# OneMotor.net
KiCad netlist of a schematic drawn in Altium Designer
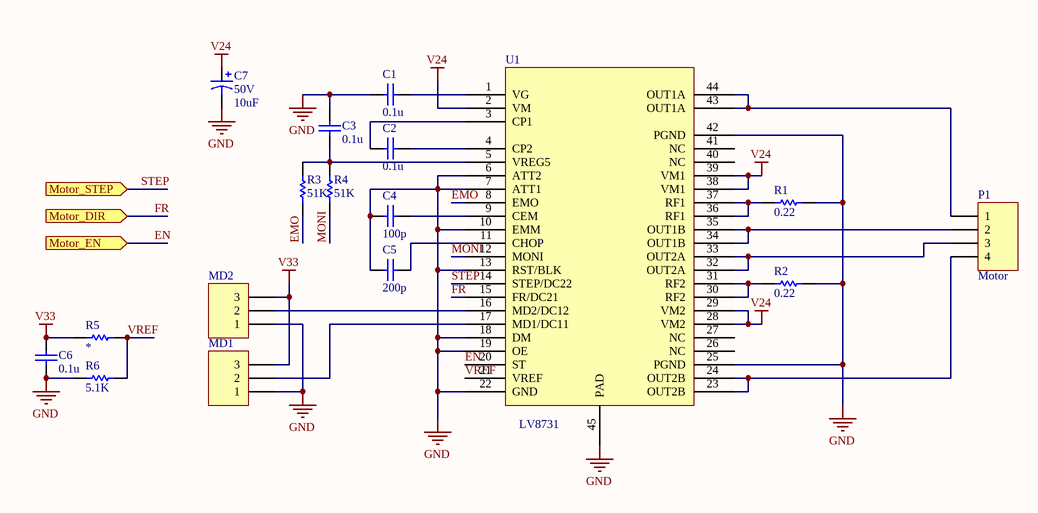
[diagram p0: OneMotor.SchDoc]

(export (version "E")
  (design (tool "Eeschema 10.0.6"))
  (components
    (comp (ref "C1")
      (value "0.1u")
      (footprint "C-1608[0603]")
      (description "Capacitor (Semiconductor SIM Model)")
      (fields (field (name "Comment") "Cap Semi") (field (name "PUBLISHER") "Altium Limited"))
      (libsource (lib "Miscellaneous Devices") (part "Cap Semi"))
    )
    (comp (ref "C2")
      (value "0.1u")
      (footprint "C-1608[0603]")
      (description "Capacitor (Semiconductor SIM Model)")
      (fields (field (name "Comment") "Cap Semi") (field (name "PUBLISHER") "Altium Limited"))
      (libsource (lib "Miscellaneous Devices") (part "Cap Semi"))
    )
    (comp (ref "C3")
      (value "0.1u")
      (footprint "C-1608[0603]")
      (description "Capacitor (Semiconductor SIM Model)")
      (fields (field (name "Comment") "Cap Semi") (field (name "PUBLISHER") "Altium Limited"))
      (libsource (lib "Miscellaneous Devices") (part "Cap Semi"))
    )
    (comp (ref "C4")
      (value "100p")
      (footprint "C-1608[0603]")
      (description "Capacitor (Semiconductor SIM Model)")
      (fields (field (name "Comment") "Cap Semi") (field (name "PUBLISHER") "Altium Limited"))
      (libsource (lib "Miscellaneous Devices") (part "Cap Semi"))
    )
    (comp (ref "C5")
      (value "200p")
      (footprint "C-1608[0603]")
      (description "Capacitor (Semiconductor SIM Model)")
      (fields (field (name "Comment") "Cap Semi") (field (name "PUBLISHER") "Altium Limited"))
      (libsource (lib "Miscellaneous Devices") (part "Cap Semi"))
    )
    (comp (ref "C6")
      (value "0.1u")
      (footprint "C-1608[0603]")
      (description "Capacitor (Semiconductor SIM Model)")
      (fields (field (name "Comment") "Cap Semi") (field (name "PUBLISHER") "Altium Limited"))
      (libsource (lib "Miscellaneous Devices") (part "Cap Semi"))
    )
    (comp (ref "C7")
      (value "50V")
      (footprint "RB.1/.25")
      (description "Polarized Capacitor (Radial)")
      (fields (field (name "ALTIUM_VALUE") "10uF") (field (name "PUBLISHER") "Altium Limited"))
      (libsource (lib "Miscellaneous Devices") (part "Cap Pol1"))
    )
    (comp (ref "MD1")
      (value "Header 3")
      (footprint "shortPad")
      (description "Header, 3-Pin")
      (fields (field (name "PUBLISHER") "Altium Limited"))
      (libsource (lib "Miscellaneous Connectors") (part "Header 3"))
    )
    (comp (ref "MD2")
      (value "Header 3")
      (footprint "shortPad")
      (description "Header, 3-Pin")
      (fields (field (name "PUBLISHER") "Altium Limited"))
      (libsource (lib "Miscellaneous Connectors") (part "Header 3"))
    )
    (comp (ref "P1")
      (value "Motor")
      (footprint "HDR1X4")
      (description "Header, 4-Pin")
      (fields (field (name "PUBLISHER") "Altium Limited"))
      (libsource (lib "Miscellaneous Connectors") (part "Header 4"))
    )
    (comp (ref "R1")
      (value "0.22")
      (footprint "R-6332[2512]")
      (description "Semiconductor Resistor")
      (fields (field (name "Comment") "Res Semi") (field (name "PUBLISHER") "Altium Limited"))
      (libsource (lib "Miscellaneous Devices") (part "Res Semi"))
    )
    (comp (ref "R2")
      (value "0.22")
      (footprint "R-6332[2512]")
      (description "Semiconductor Resistor")
      (fields (field (name "Comment") "Res Semi") (field (name "PUBLISHER") "Altium Limited"))
      (libsource (lib "Miscellaneous Devices") (part "Res Semi"))
    )
    (comp (ref "R3")
      (value "51K")
      (footprint "R-1608[0603]")
      (description "Semiconductor Resistor")
      (fields (field (name "Comment") "Res Semi") (field (name "PUBLISHER") "Altium Limited"))
      (libsource (lib "Miscellaneous Devices") (part "Res Semi"))
    )
    (comp (ref "R4")
      (value "51K")
      (footprint "R-1608[0603]")
      (description "Semiconductor Resistor")
      (fields (field (name "Comment") "Res Semi") (field (name "PUBLISHER") "Altium Limited"))
      (libsource (lib "Miscellaneous Devices") (part "Res Semi"))
    )
    (comp (ref "R5")
      (value "Res Semi")
      (footprint "R-1608[0603]")
      (description "Semiconductor Resistor")
      (fields (field (name "ALTIUM_VALUE") "*") (field (name "PUBLISHER") "Altium Limited"))
      (libsource (lib "Miscellaneous Devices") (part "Res Semi"))
    )
    (comp (ref "R6")
      (value "5.1K")
      (footprint "R-1608[0603]")
      (description "Semiconductor Resistor")
      (fields (field (name "Comment") "Res Semi") (field (name "PUBLISHER") "Altium Limited"))
      (libsource (lib "Miscellaneous Devices") (part "Res Semi"))
    )
    (comp (ref "U1") (value "LV8731") (footprint "LV8731_V3") (libsource (lib "Schlib1") (part "LV8731")))
  )
  (nets
    (net (code "1") (name "/EMO") (class "Default")
      (node (ref "R3") (pin "1") (pinfunction "1_1") (pintype "passive"))
      (node (ref "U1") (pin "8") (pinfunction "EMO_8") (pintype "passive"))
    )
    (net (code "2") (name "/EN") (class "Default")
      (node (ref "U1") (pin "20") (pinfunction "ST_20") (pintype "passive"))
    )
    (net (code "3") (name "/FR") (class "Default")
      (node (ref "U1") (pin "15") (pinfunction "FR/DC21_15") (pintype "passive"))
    )
    (net (code "4") (name "/MONI") (class "Default")
      (node (ref "R4") (pin "1") (pinfunction "1_1") (pintype "passive"))
      (node (ref "U1") (pin "12") (pinfunction "MONI_12") (pintype "passive"))
    )
    (net (code "5") (name "/STEP") (class "Default")
      (node (ref "U1") (pin "14") (pinfunction "STEP/DC22_14") (pintype "passive"))
    )
    (net (code "6") (name "/VREF") (class "Default")
      (node (ref "R5") (pin "2") (pinfunction "2_2") (pintype "passive"))
      (node (ref "R6") (pin "2") (pinfunction "2_2") (pintype "passive"))
      (node (ref "U1") (pin "21") (pinfunction "VREF_21") (pintype "passive"))
    )
    (net (code "7") (name "GND") (class "Default")
      (node (ref "C1") (pin "2") (pinfunction "2_2") (pintype "passive"))
      (node (ref "C3") (pin "1") (pinfunction "1_1") (pintype "passive"))
      (node (ref "C4") (pin "1") (pinfunction "1_1") (pintype "passive"))
      (node (ref "C5") (pin "1") (pinfunction "1_1") (pintype "passive"))
      (node (ref "C6") (pin "1") (pinfunction "1_1") (pintype "passive"))
      (node (ref "C7") (pin "2") (pinfunction "2_2") (pintype "passive"))
      (node (ref "MD1") (pin "1") (pinfunction "1_1") (pintype "passive"))
      (node (ref "MD2") (pin "1") (pinfunction "1_1") (pintype "passive"))
      (node (ref "R1") (pin "1") (pinfunction "1_1") (pintype "passive"))
      (node (ref "R2") (pin "1") (pinfunction "1_1") (pintype "passive"))
      (node (ref "R6") (pin "1") (pinfunction "1_1") (pintype "passive"))
      (node (ref "U1") (pin "10") (pinfunction "EMM_10") (pintype "passive"))
      (node (ref "U1") (pin "13") (pinfunction "RST/BLK_13") (pintype "passive"))
      (node (ref "U1") (pin "18") (pinfunction "DM_18") (pintype "passive"))
      (node (ref "U1") (pin "19") (pinfunction "OE_19") (pintype "passive"))
      (node (ref "U1") (pin "22") (pinfunction "GND_22") (pintype "passive"))
      (node (ref "U1") (pin "25") (pinfunction "PGND_25") (pintype "passive"))
      (node (ref "U1") (pin "42") (pinfunction "PGND_42") (pintype "passive"))
      (node (ref "U1") (pin "45") (pinfunction "PAD_45") (pintype "passive"))
      (node (ref "U1") (pin "6") (pinfunction "ATT2_6") (pintype "passive"))
      (node (ref "U1") (pin "7") (pinfunction "ATT1_7") (pintype "passive"))
    )
    (net (code "8") (name "Net-(P1-Pad1)") (class "Default")
      (node (ref "P1") (pin "1") (pinfunction "1_1") (pintype "passive"))
      (node (ref "U1") (pin "43") (pinfunction "OUT1A_43") (pintype "passive"))
      (node (ref "U1") (pin "44") (pinfunction "OUT1A_44") (pintype "passive"))
    )
    (net (code "9") (name "Net-(P1-Pad2)") (class "Default")
      (node (ref "P1") (pin "2") (pinfunction "2_2") (pintype "passive"))
      (node (ref "U1") (pin "34") (pinfunction "OUT1B_34") (pintype "passive"))
      (node (ref "U1") (pin "35") (pinfunction "OUT1B_35") (pintype "passive"))
    )
    (net (code "10") (name "Net-(P1-Pad3)") (class "Default")
      (node (ref "P1") (pin "3") (pinfunction "3_3") (pintype "passive"))
      (node (ref "U1") (pin "32") (pinfunction "OUT2A_32") (pintype "passive"))
      (node (ref "U1") (pin "33") (pinfunction "OUT2A_33") (pintype "passive"))
    )
    (net (code "11") (name "Net-(P1-Pad4)") (class "Default")
      (node (ref "P1") (pin "4") (pinfunction "4_4") (pintype "passive"))
      (node (ref "U1") (pin "23") (pinfunction "OUT2B_23") (pintype "passive"))
      (node (ref "U1") (pin "24") (pinfunction "OUT2B_24") (pintype "passive"))
    )
    (net (code "12") (name "Net-(R1-Pad2)") (class "Default")
      (node (ref "R1") (pin "2") (pinfunction "2_2") (pintype "passive"))
      (node (ref "U1") (pin "36") (pinfunction "RF1_36") (pintype "passive"))
      (node (ref "U1") (pin "37") (pinfunction "RF1_37") (pintype "passive"))
    )
    (net (code "13") (name "Net-(R2-Pad2)") (class "Default")
      (node (ref "R2") (pin "2") (pinfunction "2_2") (pintype "passive"))
      (node (ref "U1") (pin "30") (pinfunction "RF2_30") (pintype "passive"))
      (node (ref "U1") (pin "31") (pinfunction "RF2_31") (pintype "passive"))
    )
    (net (code "14") (name "Net-(U1-CEM)") (class "Default")
      (node (ref "C4") (pin "2") (pinfunction "2_2") (pintype "passive"))
      (node (ref "U1") (pin "9") (pinfunction "CEM_9") (pintype "passive"))
    )
    (net (code "15") (name "Net-(U1-CHOP)") (class "Default")
      (node (ref "C5") (pin "2") (pinfunction "2_2") (pintype "passive"))
      (node (ref "U1") (pin "11") (pinfunction "CHOP_11") (pintype "passive"))
    )
    (net (code "16") (name "Net-(U1-CP1)") (class "Default")
      (node (ref "C2") (pin "2") (pinfunction "2_2") (pintype "passive"))
      (node (ref "U1") (pin "3") (pinfunction "CP1_3") (pintype "passive"))
    )
    (net (code "17") (name "Net-(U1-CP2)") (class "Default")
      (node (ref "C2") (pin "1") (pinfunction "1_1") (pintype "passive"))
      (node (ref "U1") (pin "4") (pinfunction "CP2_4") (pintype "passive"))
    )
    (net (code "18") (name "Net-(U1-MD1{slash}DC11)") (class "Default")
      (node (ref "MD1") (pin "2") (pinfunction "2_2") (pintype "passive"))
      (node (ref "U1") (pin "17") (pinfunction "MD1/DC11_17") (pintype "passive"))
    )
    (net (code "19") (name "Net-(U1-MD2{slash}DC12)") (class "Default")
      (node (ref "MD2") (pin "2") (pinfunction "2_2") (pintype "passive"))
      (node (ref "U1") (pin "16") (pinfunction "MD2/DC12_16") (pintype "passive"))
    )
    (net (code "20") (name "Net-(U1-VG)") (class "Default")
      (node (ref "C1") (pin "1") (pinfunction "1_1") (pintype "passive"))
      (node (ref "U1") (pin "1") (pinfunction "VG_1") (pintype "passive"))
    )
    (net (code "21") (name "Net-(U1-VREG5)") (class "Default")
      (node (ref "C3") (pin "2") (pinfunction "2_2") (pintype "passive"))
      (node (ref "R3") (pin "2") (pinfunction "2_2") (pintype "passive"))
      (node (ref "R4") (pin "2") (pinfunction "2_2") (pintype "passive"))
      (node (ref "U1") (pin "5") (pinfunction "VREG5_5") (pintype "passive"))
    )
    (net (code "22") (name "V24") (class "Default")
      (node (ref "C7") (pin "1") (pinfunction "1_1") (pintype "passive"))
      (node (ref "U1") (pin "2") (pinfunction "VM_2") (pintype "passive"))
      (node (ref "U1") (pin "28") (pinfunction "VM2_28") (pintype "passive"))
      (node (ref "U1") (pin "29") (pinfunction "VM2_29") (pintype "passive"))
      (node (ref "U1") (pin "38") (pinfunction "VM1_38") (pintype "passive"))
      (node (ref "U1") (pin "39") (pinfunction "VM1_39") (pintype "passive"))
    )
    (net (code "23") (name "V33") (class "Default")
      (node (ref "C6") (pin "2") (pinfunction "2_2") (pintype "passive"))
      (node (ref "MD1") (pin "3") (pinfunction "3_3") (pintype "passive"))
      (node (ref "MD2") (pin "3") (pinfunction "3_3") (pintype "passive"))
      (node (ref "R5") (pin "1") (pinfunction "1_1") (pintype "passive"))
    )
    (net (code "24") (name "unconnected-(U1-NC-Pad26)") (class "Default")
      (node (ref "U1") (pin "26") (pinfunction "NC_26") (pintype "passive"))
    )
    (net (code "25") (name "unconnected-(U1-NC-Pad27)") (class "Default")
      (node (ref "U1") (pin "27") (pinfunction "NC_27") (pintype "passive"))
    )
    (net (code "26") (name "unconnected-(U1-NC-Pad40)") (class "Default")
      (node (ref "U1") (pin "40") (pinfunction "NC_40") (pintype "passive"))
    )
    (net (code "27") (name "unconnected-(U1-NC-Pad41)") (class "Default")
      (node (ref "U1") (pin "41") (pinfunction "NC_41") (pintype "passive"))
    )
  )
)
